# ARMBAND.net
KiCad netlist of a schematic drawn in Altium Designer
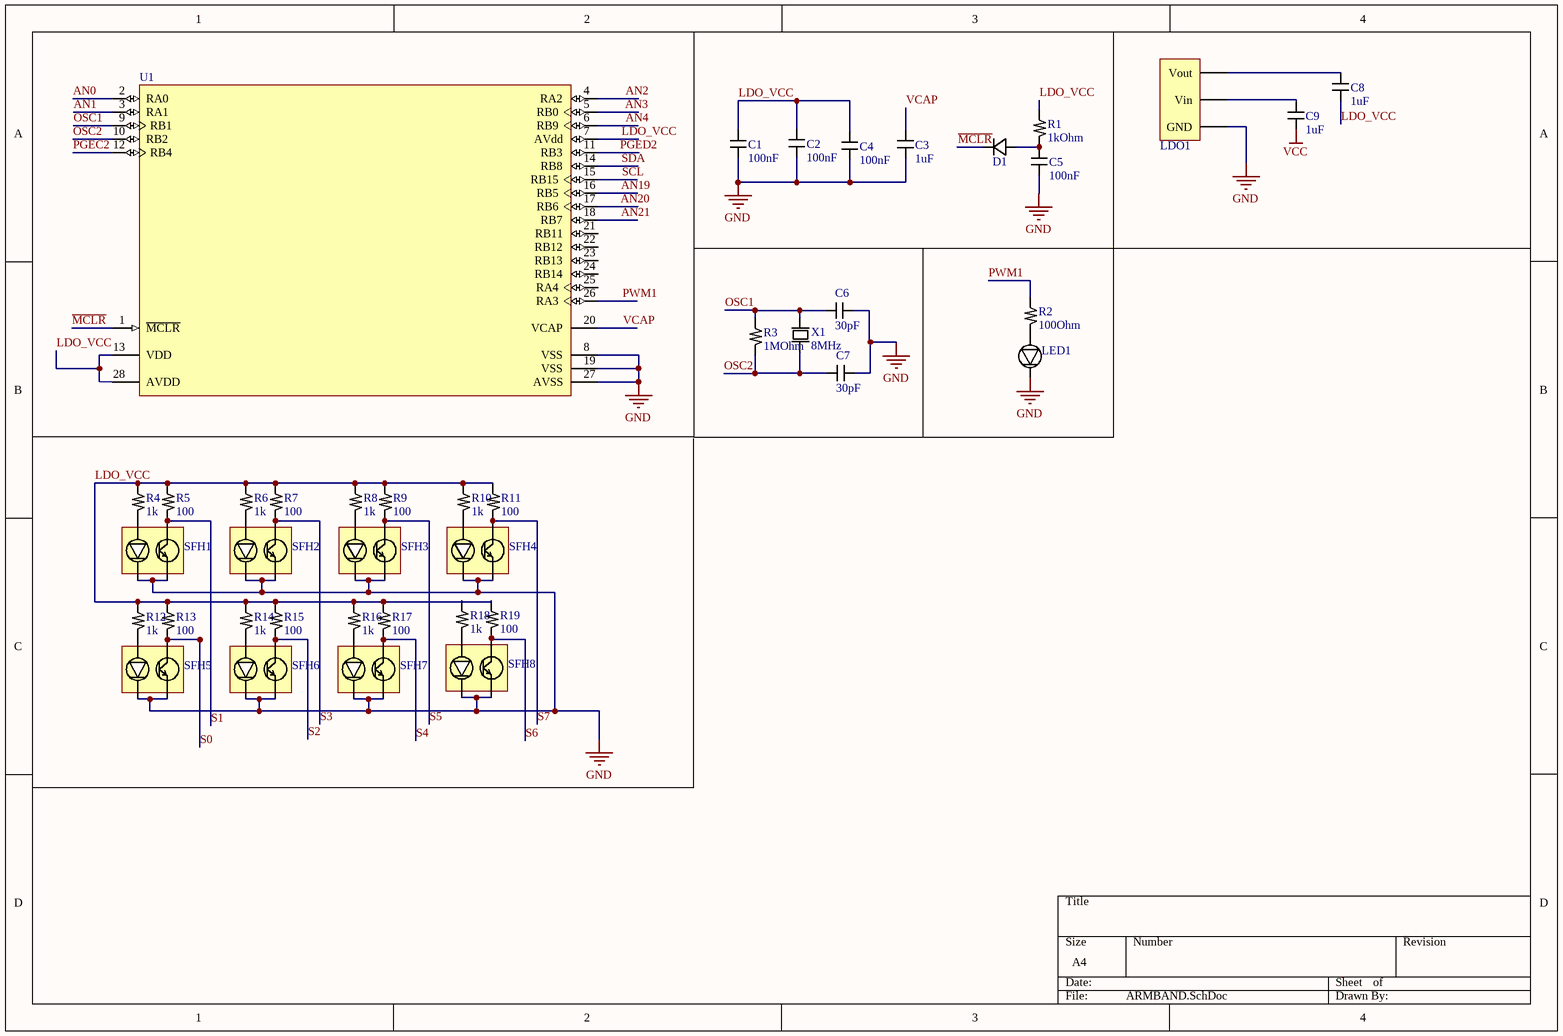
[diagram p0: ARMBAND.SchDoc]

(export (version "E")
  (design (tool "Eeschema 10.0.6"))
  (components
    (comp (ref "C1")
      (value "100nF")
      (footprint "CApacitor_1608")
      (description "SMD Capacitor")
      (libsource (lib "ARMBand_Components") (part "Capacitor_SMD"))
    )
    (comp (ref "C2")
      (value "100nF")
      (footprint "CApacitor_1608")
      (description "SMD Capacitor")
      (libsource (lib "ARMBand_Components") (part "Capacitor_SMD"))
    )
    (comp (ref "C3")
      (value "1uF")
      (footprint "Capacitor_20x12")
      (description "SMD Capacitor")
      (libsource (lib "ARMBand_Components") (part "Capacitor_SMD"))
    )
    (comp (ref "C4")
      (value "100nF")
      (footprint "CApacitor_1608")
      (description "SMD Capacitor")
      (libsource (lib "ARMBand_Components") (part "Capacitor_SMD"))
    )
    (comp (ref "C5")
      (value "100nF")
      (footprint "CApacitor_1608")
      (description "SMD Capacitor")
      (libsource (lib "ARMBand_Components") (part "Capacitor_SMD"))
    )
    (comp (ref "C6")
      (value "30pF")
      (footprint "CApacitor_1608")
      (description "SMD Capacitor")
      (libsource (lib "ARMBand_Components") (part "Capacitor_SMD"))
    )
    (comp (ref "C7")
      (value "30pF")
      (footprint "CApacitor_1608")
      (description "SMD Capacitor")
      (libsource (lib "ARMBand_Components") (part "Capacitor_SMD"))
    )
    (comp (ref "C8")
      (value "1uF")
      (footprint "Capacitor_20x12")
      (description "SMD Capacitor")
      (libsource (lib "ARMBand_Components") (part "Capacitor_SMD"))
    )
    (comp (ref "C9")
      (value "1uF")
      (footprint "Capacitor_20x12")
      (description "SMD Capacitor")
      (libsource (lib "ARMBand_Components") (part "Capacitor_SMD"))
    )
    (comp (ref "D1")
      (value "Diode_SMD")
      (footprint "DIODE_17x38")
      (description "SMD Diode")
      (libsource (lib "ARMBand_Components") (part "Diode_SMD"))
    )
    (comp (ref "LDO1")
      (value "Voltage Reg.")
      (footprint "LDO_460x260")
      (description "LDO Voltage Regulator")
      (libsource (lib "ARMBand_Components") (part "Voltage_Regulator_3.3V"))
    )
    (comp (ref "LED1")
      (value "LED_SMD")
      (footprint "LED_1608")
      (description "SMD Blue LED")
      (libsource (lib "ARMBand_Components") (part "LED_SMD"))
    )
    (comp (ref "R1")
      (value "1kOhm")
      (footprint "Resistor_1608")
      (description "SMD Resistor")
      (libsource (lib "ARMBand_Components") (part "Resistor_SMD"))
    )
    (comp (ref "R2")
      (value "100Ohm")
      (footprint "Resistor_1608")
      (description "SMD Resistor")
      (libsource (lib "ARMBand_Components") (part "Resistor_SMD"))
    )
    (comp (ref "R3")
      (value "1MOhm")
      (footprint "Resistor_1608")
      (description "SMD Resistor")
      (libsource (lib "ARMBand_Components") (part "Resistor_SMD"))
    )
    (comp (ref "R4")
      (value "1k")
      (footprint "Resistor_1608")
      (description "SMD Resistor")
      (libsource (lib "ARMBand_Components") (part "Resistor_SMD"))
    )
    (comp (ref "R5")
      (value "100")
      (footprint "Resistor_1608")
      (description "SMD Resistor")
      (libsource (lib "ARMBand_Components") (part "Resistor_SMD"))
    )
    (comp (ref "R6")
      (value "1k")
      (footprint "Resistor_1608")
      (description "SMD Resistor")
      (libsource (lib "ARMBand_Components") (part "Resistor_SMD"))
    )
    (comp (ref "R7")
      (value "100")
      (footprint "Resistor_1608")
      (description "SMD Resistor")
      (libsource (lib "ARMBand_Components") (part "Resistor_SMD"))
    )
    (comp (ref "R8")
      (value "1k")
      (footprint "Resistor_1608")
      (description "SMD Resistor")
      (libsource (lib "ARMBand_Components") (part "Resistor_SMD"))
    )
    (comp (ref "R9")
      (value "100")
      (footprint "Resistor_1608")
      (description "SMD Resistor")
      (libsource (lib "ARMBand_Components") (part "Resistor_SMD"))
    )
    (comp (ref "R10")
      (value "1k")
      (footprint "Resistor_1608")
      (description "SMD Resistor")
      (libsource (lib "ARMBand_Components") (part "Resistor_SMD"))
    )
    (comp (ref "R11")
      (value "100")
      (footprint "Resistor_1608")
      (description "SMD Resistor")
      (libsource (lib "ARMBand_Components") (part "Resistor_SMD"))
    )
    (comp (ref "R12")
      (value "1k")
      (footprint "Resistor_1608")
      (description "SMD Resistor")
      (libsource (lib "ARMBand_Components") (part "Resistor_SMD"))
    )
    (comp (ref "R13")
      (value "100")
      (footprint "Resistor_1608")
      (description "SMD Resistor")
      (libsource (lib "ARMBand_Components") (part "Resistor_SMD"))
    )
    (comp (ref "R14")
      (value "1k")
      (footprint "Resistor_1608")
      (description "SMD Resistor")
      (libsource (lib "ARMBand_Components") (part "Resistor_SMD"))
    )
    (comp (ref "R15")
      (value "100")
      (footprint "Resistor_1608")
      (description "SMD Resistor")
      (libsource (lib "ARMBand_Components") (part "Resistor_SMD"))
    )
    (comp (ref "R16")
      (value "1k")
      (footprint "Resistor_1608")
      (description "SMD Resistor")
      (libsource (lib "ARMBand_Components") (part "Resistor_SMD"))
    )
    (comp (ref "R17")
      (value "100")
      (footprint "Resistor_1608")
      (description "SMD Resistor")
      (libsource (lib "ARMBand_Components") (part "Resistor_SMD"))
    )
    (comp (ref "R18")
      (value "1k")
      (footprint "Resistor_1608")
      (description "SMD Resistor")
      (libsource (lib "ARMBand_Components") (part "Resistor_SMD"))
    )
    (comp (ref "R19")
      (value "100")
      (footprint "Resistor_1608")
      (description "SMD Resistor")
      (libsource (lib "ARMBand_Components") (part "Resistor_SMD"))
    )
    (comp (ref "SFH1")
      (value "SFH 7250")
      (footprint "SFH_SENSOR_34x30")
      (description "Infrared Emitter - PhTransistor Receiver")
      (libsource (lib "ARMBand_Components") (part "SFH_7250_Sensor"))
    )
    (comp (ref "SFH2")
      (value "SFH 7250")
      (footprint "SFH_SENSOR_34x30")
      (description "Infrared Emitter - PhTransistor Receiver")
      (libsource (lib "ARMBand_Components") (part "SFH_7250_Sensor"))
    )
    (comp (ref "SFH3")
      (value "SFH 7250")
      (footprint "SFH_SENSOR_34x30")
      (description "Infrared Emitter - PhTransistor Receiver")
      (libsource (lib "ARMBand_Components") (part "SFH_7250_Sensor"))
    )
    (comp (ref "SFH4")
      (value "SFH 7250")
      (footprint "SFH_SENSOR_34x30")
      (description "Infrared Emitter - PhTransistor Receiver")
      (libsource (lib "ARMBand_Components") (part "SFH_7250_Sensor"))
    )
    (comp (ref "SFH5")
      (value "SFH 7250")
      (footprint "SFH_SENSOR_34x30")
      (description "Infrared Emitter - PhTransistor Receiver")
      (libsource (lib "ARMBand_Components") (part "SFH_7250_Sensor"))
    )
    (comp (ref "SFH6")
      (value "SFH 7250")
      (footprint "SFH_SENSOR_34x30")
      (description "Infrared Emitter - PhTransistor Receiver")
      (libsource (lib "ARMBand_Components") (part "SFH_7250_Sensor"))
    )
    (comp (ref "SFH7")
      (value "SFH 7250")
      (footprint "SFH_SENSOR_34x30")
      (description "Infrared Emitter - PhTransistor Receiver")
      (libsource (lib "ARMBand_Components") (part "SFH_7250_Sensor"))
    )
    (comp (ref "SFH8")
      (value "SFH 7250")
      (footprint "SFH_SENSOR_34x30")
      (description "Infrared Emitter - PhTransistor Receiver")
      (libsource (lib "ARMBand_Components") (part "SFH_7250_Sensor"))
    )
    (comp (ref "U1")
      (value "DSPIC33EP128MC202-I/SO")
      (footprint "MCHP-SOIC-SO28_N")
      (fields (field (name "MANUFACTURER") "Microchip"))
      (libsource (lib "Microchip dsPIC33E") (part "DSPIC33EP128MC202-I/SO"))
    )
    (comp (ref "X1")
      (value "8MHz")
      (footprint "xTal_150x20")
      (description "8MHz Crystal/Resonator")
      (libsource (lib "ARMBand_Components") (part "xTal_ECS_inc"))
    )
  )
  (nets
    (net (code "2") (name "/AN0") (class "Default")
      (node (ref "U1") (pin "2") (pinfunction "RA0_2") (pintype "bidirectional"))
    )
    (net (code "3") (name "/AN1") (class "Default")
      (node (ref "U1") (pin "3") (pinfunction "RA1_3") (pintype "bidirectional"))
    )
    (net (code "4") (name "/AN2") (class "Default")
      (node (ref "U1") (pin "4") (pinfunction "RA2_4") (pintype "bidirectional"))
    )
    (net (code "5") (name "/AN3") (class "Default")
      (node (ref "U1") (pin "5") (pinfunction "RB0_5") (pintype "bidirectional"))
    )
    (net (code "6") (name "/AN4") (class "Default")
      (node (ref "U1") (pin "6") (pinfunction "RB9_6") (pintype "bidirectional"))
    )
    (net (code "7") (name "/AN19") (class "Default")
      (node (ref "U1") (pin "16") (pinfunction "RB5_16") (pintype "bidirectional"))
    )
    (net (code "8") (name "/AN20") (class "Default")
      (node (ref "U1") (pin "17") (pinfunction "RB6_17") (pintype "bidirectional"))
    )
    (net (code "9") (name "/AN21") (class "Default")
      (node (ref "U1") (pin "18") (pinfunction "RB7_18") (pintype "bidirectional"))
    )
    (net (code "10") (name "/LDO_VCC") (class "Default")
      (node (ref "C1") (pin "Cap_p1") (pinfunction "Cap_p1_Cap_p1") (pintype "passive"))
      (node (ref "C2") (pin "Cap_p1") (pinfunction "Cap_p1_Cap_p1") (pintype "passive"))
      (node (ref "C4") (pin "Cap_p1") (pinfunction "Cap_p1_Cap_p1") (pintype "passive"))
      (node (ref "C8") (pin "Cap_p1") (pinfunction "Cap_p1_Cap_p1") (pintype "passive"))
      (node (ref "R1") (pin "Res_p1") (pinfunction "Res_p1_Res_p1") (pintype "passive"))
      (node (ref "R10") (pin "Res_p1") (pinfunction "Res_p1_Res_p1") (pintype "passive"))
      (node (ref "R11") (pin "Res_p1") (pinfunction "Res_p1_Res_p1") (pintype "passive"))
      (node (ref "R12") (pin "Res_p1") (pinfunction "Res_p1_Res_p1") (pintype "passive"))
      (node (ref "R13") (pin "Res_p1") (pinfunction "Res_p1_Res_p1") (pintype "passive"))
      (node (ref "R14") (pin "Res_p1") (pinfunction "Res_p1_Res_p1") (pintype "passive"))
      (node (ref "R15") (pin "Res_p1") (pinfunction "Res_p1_Res_p1") (pintype "passive"))
      (node (ref "R16") (pin "Res_p1") (pinfunction "Res_p1_Res_p1") (pintype "passive"))
      (node (ref "R17") (pin "Res_p1") (pinfunction "Res_p1_Res_p1") (pintype "passive"))
      (node (ref "R19") (pin "Res_p1") (pinfunction "Res_p1_Res_p1") (pintype "passive"))
      (node (ref "R4") (pin "Res_p1") (pinfunction "Res_p1_Res_p1") (pintype "passive"))
      (node (ref "R5") (pin "Res_p1") (pinfunction "Res_p1_Res_p1") (pintype "passive"))
      (node (ref "R6") (pin "Res_p1") (pinfunction "Res_p1_Res_p1") (pintype "passive"))
      (node (ref "R7") (pin "Res_p1") (pinfunction "Res_p1_Res_p1") (pintype "passive"))
      (node (ref "R8") (pin "Res_p1") (pinfunction "Res_p1_Res_p1") (pintype "passive"))
      (node (ref "R9") (pin "Res_p1") (pinfunction "Res_p1_Res_p1") (pintype "passive"))
      (node (ref "U1") (pin "13") (pinfunction "VDD_13") (pintype "power_in"))
      (node (ref "U1") (pin "28") (pinfunction "AVDD_28") (pintype "power_in"))
      (node (ref "U1") (pin "7") (pinfunction "AVdd_7") (pintype "bidirectional"))
    )
    (net (code "11") (name "/OSC1") (class "Default")
      (node (ref "C6") (pin "Cap_p2") (pinfunction "Cap_p2_Cap_p2") (pintype "passive"))
      (node (ref "R3") (pin "Res_p1") (pinfunction "Res_p1_Res_p1") (pintype "passive"))
      (node (ref "U1") (pin "9") (pinfunction "RB1_9") (pintype "bidirectional"))
      (node (ref "X1") (pin "xTal_0") (pinfunction "xTal_0_xTal_0") (pintype "passive"))
    )
    (net (code "12") (name "/OSC2") (class "Default")
      (node (ref "C7") (pin "Cap_p2") (pinfunction "Cap_p2_Cap_p2") (pintype "passive"))
      (node (ref "R3") (pin "Res_p2") (pinfunction "Res_p2_Res_p2") (pintype "passive"))
      (node (ref "U1") (pin "10") (pinfunction "RB2_10") (pintype "bidirectional"))
      (node (ref "X1") (pin "xTal_1") (pinfunction "xTal_1_xTal_1") (pintype "passive"))
    )
    (net (code "13") (name "/PGEC2") (class "Default")
      (node (ref "U1") (pin "12") (pinfunction "RB4_12") (pintype "bidirectional"))
    )
    (net (code "14") (name "/PGED2") (class "Default")
      (node (ref "U1") (pin "11") (pinfunction "RB3_11") (pintype "bidirectional"))
    )
    (net (code "15") (name "/PWM1") (class "Default")
      (node (ref "R2") (pin "Res_p1") (pinfunction "Res_p1_Res_p1") (pintype "passive"))
      (node (ref "U1") (pin "26") (pinfunction "RA3_26") (pintype "bidirectional"))
    )
    (net (code "16") (name "/S0") (class "Default")
      (node (ref "R13") (pin "Res_p2") (pinfunction "Res_p2_Res_p2") (pintype "passive"))
      (node (ref "SFH5") (pin "PhT_Collector") (pinfunction "PhT_Collector_PhT_Collector") (pintype "passive"))
    )
    (net (code "17") (name "/S1") (class "Default")
      (node (ref "R5") (pin "Res_p2") (pinfunction "Res_p2_Res_p2") (pintype "passive"))
      (node (ref "SFH1") (pin "PhT_Collector") (pinfunction "PhT_Collector_PhT_Collector") (pintype "passive"))
    )
    (net (code "18") (name "/S2") (class "Default")
      (node (ref "R15") (pin "Res_p2") (pinfunction "Res_p2_Res_p2") (pintype "passive"))
      (node (ref "SFH6") (pin "PhT_Collector") (pinfunction "PhT_Collector_PhT_Collector") (pintype "passive"))
    )
    (net (code "19") (name "/S3") (class "Default")
      (node (ref "R7") (pin "Res_p2") (pinfunction "Res_p2_Res_p2") (pintype "passive"))
      (node (ref "SFH2") (pin "PhT_Collector") (pinfunction "PhT_Collector_PhT_Collector") (pintype "passive"))
    )
    (net (code "20") (name "/S4") (class "Default")
      (node (ref "R17") (pin "Res_p2") (pinfunction "Res_p2_Res_p2") (pintype "passive"))
      (node (ref "SFH7") (pin "PhT_Collector") (pinfunction "PhT_Collector_PhT_Collector") (pintype "passive"))
    )
    (net (code "21") (name "/S5") (class "Default")
      (node (ref "R9") (pin "Res_p2") (pinfunction "Res_p2_Res_p2") (pintype "passive"))
      (node (ref "SFH3") (pin "PhT_Collector") (pinfunction "PhT_Collector_PhT_Collector") (pintype "passive"))
    )
    (net (code "22") (name "/S6") (class "Default")
      (node (ref "R19") (pin "Res_p2") (pinfunction "Res_p2_Res_p2") (pintype "passive"))
      (node (ref "SFH8") (pin "PhT_Collector") (pinfunction "PhT_Collector_PhT_Collector") (pintype "passive"))
    )
    (net (code "23") (name "/S7") (class "Default")
      (node (ref "R11") (pin "Res_p2") (pinfunction "Res_p2_Res_p2") (pintype "passive"))
      (node (ref "SFH4") (pin "PhT_Collector") (pinfunction "PhT_Collector_PhT_Collector") (pintype "passive"))
    )
    (net (code "24") (name "/SCL") (class "Default")
      (node (ref "U1") (pin "15") (pinfunction "RB15_15") (pintype "bidirectional"))
    )
    (net (code "25") (name "/SDA") (class "Default")
      (node (ref "U1") (pin "14") (pinfunction "RB8_14") (pintype "bidirectional"))
    )
    (net (code "26") (name "/VCAP") (class "Default")
      (node (ref "C3") (pin "Cap_p1") (pinfunction "Cap_p1_Cap_p1") (pintype "passive"))
      (node (ref "U1") (pin "20") (pinfunction "VCAP_20") (pintype "passive"))
    )
    (net (code "27") (name "/~{MCLR}") (class "Default")
      (node (ref "D1") (pin "Cathode") (pinfunction "Cathode_Cathode") (pintype "passive"))
      (node (ref "U1") (pin "1") (pinfunction "~{MCLR}_1") (pintype "input"))
    )
    (net (code "28") (name "GND") (class "Default")
      (node (ref "C1") (pin "Cap_p2") (pinfunction "Cap_p2_Cap_p2") (pintype "passive"))
      (node (ref "C2") (pin "Cap_p2") (pinfunction "Cap_p2_Cap_p2") (pintype "passive"))
      (node (ref "C3") (pin "Cap_p2") (pinfunction "Cap_p2_Cap_p2") (pintype "passive"))
      (node (ref "C4") (pin "Cap_p2") (pinfunction "Cap_p2_Cap_p2") (pintype "passive"))
      (node (ref "C5") (pin "Cap_p2") (pinfunction "Cap_p2_Cap_p2") (pintype "passive"))
      (node (ref "C6") (pin "Cap_p1") (pinfunction "Cap_p1_Cap_p1") (pintype "passive"))
      (node (ref "C7") (pin "Cap_p1") (pinfunction "Cap_p1_Cap_p1") (pintype "passive"))
      (node (ref "LDO1") (pin "GND") (pinfunction "GND_GND") (pintype "passive"))
      (node (ref "LED1") (pin "Cathode") (pinfunction "Cathode_Cathode") (pintype "passive"))
      (node (ref "SFH1") (pin "LED_Cathode") (pinfunction "LED_Cathode_LED_Cathode") (pintype "passive"))
      (node (ref "SFH1") (pin "PhT_Emitter") (pinfunction "PhT_Emitter_PhT_Emitter") (pintype "passive"))
      (node (ref "SFH2") (pin "LED_Cathode") (pinfunction "LED_Cathode_LED_Cathode") (pintype "passive"))
      (node (ref "SFH2") (pin "PhT_Emitter") (pinfunction "PhT_Emitter_PhT_Emitter") (pintype "passive"))
      (node (ref "SFH3") (pin "LED_Cathode") (pinfunction "LED_Cathode_LED_Cathode") (pintype "passive"))
      (node (ref "SFH3") (pin "PhT_Emitter") (pinfunction "PhT_Emitter_PhT_Emitter") (pintype "passive"))
      (node (ref "SFH4") (pin "LED_Cathode") (pinfunction "LED_Cathode_LED_Cathode") (pintype "passive"))
      (node (ref "SFH4") (pin "PhT_Emitter") (pinfunction "PhT_Emitter_PhT_Emitter") (pintype "passive"))
      (node (ref "SFH5") (pin "LED_Cathode") (pinfunction "LED_Cathode_LED_Cathode") (pintype "passive"))
      (node (ref "SFH5") (pin "PhT_Emitter") (pinfunction "PhT_Emitter_PhT_Emitter") (pintype "passive"))
      (node (ref "SFH6") (pin "LED_Cathode") (pinfunction "LED_Cathode_LED_Cathode") (pintype "passive"))
      (node (ref "SFH6") (pin "PhT_Emitter") (pinfunction "PhT_Emitter_PhT_Emitter") (pintype "passive"))
      (node (ref "SFH7") (pin "LED_Cathode") (pinfunction "LED_Cathode_LED_Cathode") (pintype "passive"))
      (node (ref "SFH7") (pin "PhT_Emitter") (pinfunction "PhT_Emitter_PhT_Emitter") (pintype "passive"))
      (node (ref "SFH8") (pin "LED_Cathode") (pinfunction "LED_Cathode_LED_Cathode") (pintype "passive"))
      (node (ref "SFH8") (pin "PhT_Emitter") (pinfunction "PhT_Emitter_PhT_Emitter") (pintype "passive"))
      (node (ref "U1") (pin "19") (pinfunction "VSS_19") (pintype "power_in"))
      (node (ref "U1") (pin "27") (pinfunction "AVSS_27") (pintype "power_in"))
      (node (ref "U1") (pin "8") (pinfunction "VSS_8") (pintype "power_in"))
    )
    (net (code "29") (name "Net-(C5-PadCap_p1)") (class "Default")
      (node (ref "C5") (pin "Cap_p1") (pinfunction "Cap_p1_Cap_p1") (pintype "passive"))
      (node (ref "D1") (pin "Anode") (pinfunction "Anode_Anode") (pintype "passive"))
      (node (ref "R1") (pin "Res_p2") (pinfunction "Res_p2_Res_p2") (pintype "passive"))
    )
    (net (code "30") (name "Net-(C8-PadCap_p2)") (class "Default")
      (node (ref "C8") (pin "Cap_p2") (pinfunction "Cap_p2_Cap_p2") (pintype "passive"))
      (node (ref "LDO1") (pin "Vout") (pinfunction "Vout_Vout") (pintype "passive"))
    )
    (net (code "31") (name "Net-(C9-PadCap_p2)") (class "Default")
      (node (ref "C9") (pin "Cap_p2") (pinfunction "Cap_p2_Cap_p2") (pintype "passive"))
      (node (ref "LDO1") (pin "Vin") (pinfunction "Vin_Vin") (pintype "passive"))
    )
    (net (code "32") (name "Net-(LED1-PadAnode)") (class "Default")
      (node (ref "LED1") (pin "Anode") (pinfunction "Anode_Anode") (pintype "passive"))
      (node (ref "R2") (pin "Res_p2") (pinfunction "Res_p2_Res_p2") (pintype "passive"))
    )
    (net (code "33") (name "Net-(R4-PadRes_p2)") (class "Default")
      (node (ref "R4") (pin "Res_p2") (pinfunction "Res_p2_Res_p2") (pintype "passive"))
      (node (ref "SFH1") (pin "LED_Anode") (pinfunction "LED_Anode_LED_Anode") (pintype "passive"))
    )
    (net (code "34") (name "Net-(R6-PadRes_p2)") (class "Default")
      (node (ref "R6") (pin "Res_p2") (pinfunction "Res_p2_Res_p2") (pintype "passive"))
      (node (ref "SFH2") (pin "LED_Anode") (pinfunction "LED_Anode_LED_Anode") (pintype "passive"))
    )
    (net (code "35") (name "Net-(R8-PadRes_p2)") (class "Default")
      (node (ref "R8") (pin "Res_p2") (pinfunction "Res_p2_Res_p2") (pintype "passive"))
      (node (ref "SFH3") (pin "LED_Anode") (pinfunction "LED_Anode_LED_Anode") (pintype "passive"))
    )
    (net (code "36") (name "Net-(R10-PadRes_p2)") (class "Default")
      (node (ref "R10") (pin "Res_p2") (pinfunction "Res_p2_Res_p2") (pintype "passive"))
      (node (ref "SFH4") (pin "LED_Anode") (pinfunction "LED_Anode_LED_Anode") (pintype "passive"))
    )
    (net (code "37") (name "Net-(R12-PadRes_p2)") (class "Default")
      (node (ref "R12") (pin "Res_p2") (pinfunction "Res_p2_Res_p2") (pintype "passive"))
      (node (ref "SFH5") (pin "LED_Anode") (pinfunction "LED_Anode_LED_Anode") (pintype "passive"))
    )
    (net (code "38") (name "Net-(R14-PadRes_p2)") (class "Default")
      (node (ref "R14") (pin "Res_p2") (pinfunction "Res_p2_Res_p2") (pintype "passive"))
      (node (ref "SFH6") (pin "LED_Anode") (pinfunction "LED_Anode_LED_Anode") (pintype "passive"))
    )
    (net (code "39") (name "Net-(R16-PadRes_p2)") (class "Default")
      (node (ref "R16") (pin "Res_p2") (pinfunction "Res_p2_Res_p2") (pintype "passive"))
      (node (ref "SFH7") (pin "LED_Anode") (pinfunction "LED_Anode_LED_Anode") (pintype "passive"))
    )
    (net (code "40") (name "Net-(R18-PadRes_p2)") (class "Default")
      (node (ref "R18") (pin "Res_p2") (pinfunction "Res_p2_Res_p2") (pintype "passive"))
      (node (ref "SFH8") (pin "LED_Anode") (pinfunction "LED_Anode_LED_Anode") (pintype "passive"))
    )
    (net (code "41") (name "VCC") (class "Default")
      (node (ref "C9") (pin "Cap_p1") (pinfunction "Cap_p1_Cap_p1") (pintype "passive"))
    )
    (net (code "42") (name "unconnected-(R18-PadRes_p1)") (class "Default")
      (node (ref "R18") (pin "Res_p1") (pinfunction "Res_p1_Res_p1") (pintype "passive"))
    )
    (net (code "43") (name "unconnected-(U1-RA4-Pad25)") (class "Default")
      (node (ref "U1") (pin "25") (pinfunction "RA4_25") (pintype "bidirectional"))
    )
    (net (code "44") (name "unconnected-(U1-RB11-Pad21)") (class "Default")
      (node (ref "U1") (pin "21") (pinfunction "RB11_21") (pintype "bidirectional"))
    )
    (net (code "45") (name "unconnected-(U1-RB12-Pad22)") (class "Default")
      (node (ref "U1") (pin "22") (pinfunction "RB12_22") (pintype "bidirectional"))
    )
    (net (code "46") (name "unconnected-(U1-RB13-Pad23)") (class "Default")
      (node (ref "U1") (pin "23") (pinfunction "RB13_23") (pintype "bidirectional"))
    )
    (net (code "47") (name "unconnected-(U1-RB14-Pad24)") (class "Default")
      (node (ref "U1") (pin "24") (pinfunction "RB14_24") (pintype "bidirectional"))
    )
  )
)
